# MAIN_POWER.net
KiCad netlist of a schematic drawn in Altium Designer
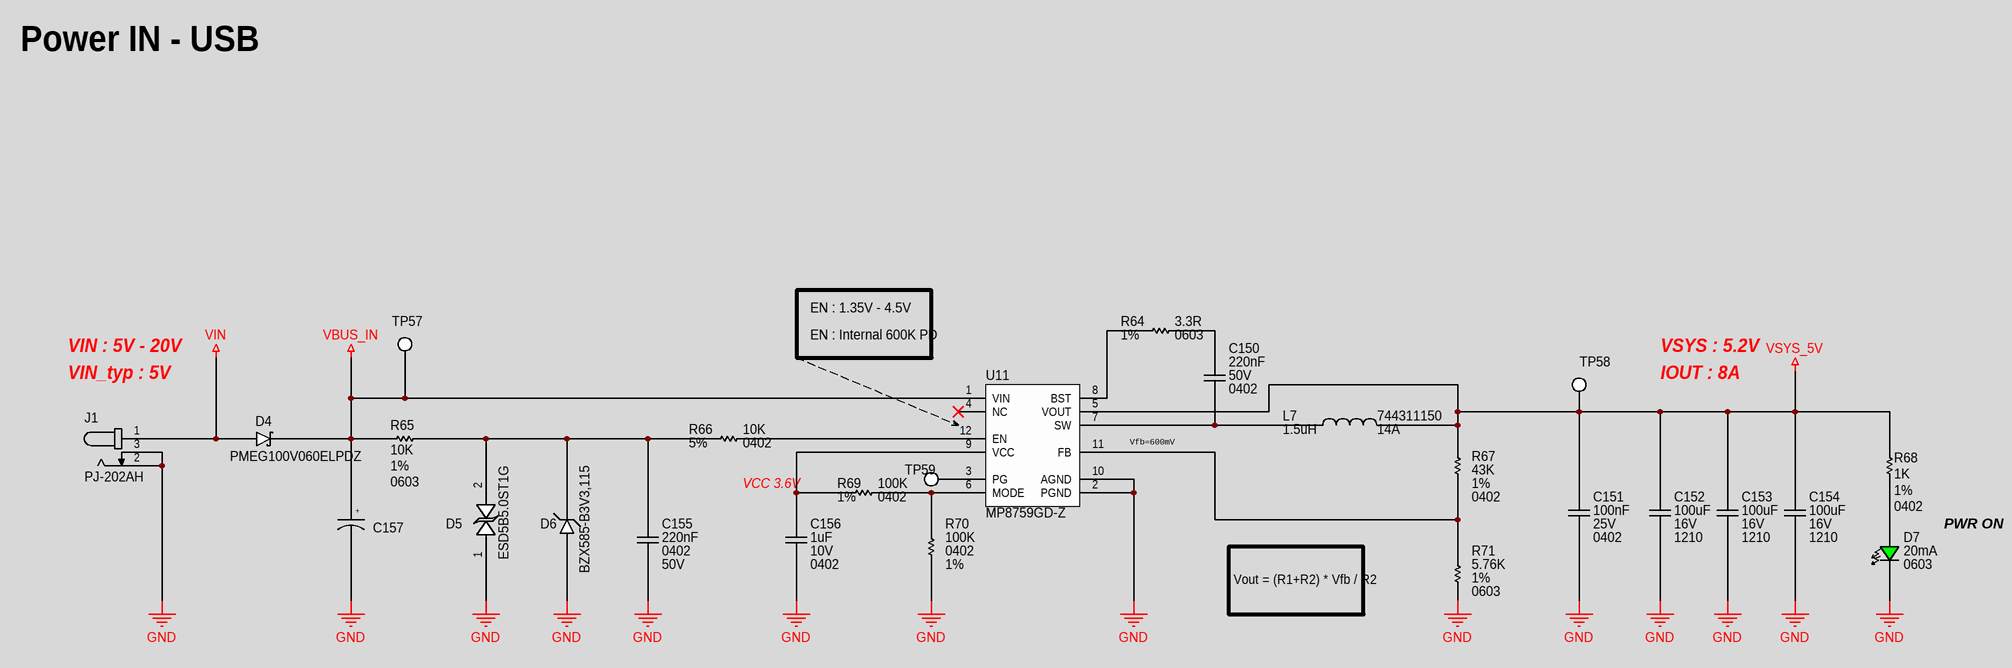
[diagram p0: MAIN_POWER.SchDoc]

(export (version "E")
  (design (tool "Eeschema 10.0.6"))
  (components
    (comp (ref "C150")
      (value "GRM155R61H224KE01W")
      (footprint "CAP_0402_CAPC1005X05N")
      (description "Multilayer Ceramic Capacitor, 0.22 uF, 50 VDC, ± 10%, X5R, 0402 [1005 Metric]")
      (fields
        (field (name "MANUFACTURER") "Murata")
        (field (name "CASE/PACKAGE") "0402")
        (field (name "VOLTAGE RATING (DC)") "50V")
        (field (name "CAPACITANCE") "220nF")
      )
      (libsource (lib "Electronic Devices_LIB") (part "CAP_0.22UF_50V_X5R_0402"))
    )
    (comp (ref "C151")
      (value "CC0402KRX5R8BB104")
      (footprint "CAP_0402_CAPC1005X05N")
      (description "Multilayer Ceramic Capacitor, 0.1 uF, 25 V, ± 10%, X7R, 0402 [1005 Metric]")
      (fields
        (field (name "MANUFACTURER") "Yageo")
        (field (name "TOLERANCE") "10%")
        (field (name "CAPACITANCE") "100nF")
        (field (name "VOLTAGE RATING") "25V")
        (field (name "CASE/PACKAGE") "0402")
      )
      (libsource (lib "Electronic Devices_LIB") (part "CAP_100NF_25V_X7R_0402"))
    )
    (comp (ref "C152")
      (value "EMK325ABJ107MM-T")
      (footprint "CAP_1210_CAPC3225X270N")
      (description "Multilayer Ceramic Capacitor, 100 uF, 16 V, ± 20%, X5R, 1210 [3225 Metric]")
      (fields
        (field (name "MANUFACTURER") "Taiyo Yuden")
        (field (name "TOLERANCE") "20%")
        (field (name "VOLTAGE RATING") "16V")
        (field (name "CAPACITANCE") "100uF")
        (field (name "CASE/PACKAGE") "1210")
      )
      (libsource (lib "Electronic Devices_LIB") (part "CAP_100UF_16V_X5R_1210"))
    )
    (comp (ref "C153")
      (value "EMK325ABJ107MM-T")
      (footprint "CAP_1210_CAPC3225X270N")
      (description "Multilayer Ceramic Capacitor, 100 uF, 16 V, ± 20%, X5R, 1210 [3225 Metric]")
      (fields
        (field (name "MANUFACTURER") "Taiyo Yuden")
        (field (name "TOLERANCE") "20%")
        (field (name "VOLTAGE RATING") "16V")
        (field (name "CAPACITANCE") "100uF")
        (field (name "CASE/PACKAGE") "1210")
      )
      (libsource (lib "Electronic Devices_LIB") (part "CAP_100UF_16V_X5R_1210"))
    )
    (comp (ref "C154")
      (value "EMK325ABJ107MM-T")
      (footprint "CAP_1210_CAPC3225X270N")
      (description "Multilayer Ceramic Capacitor, 100 uF, 16 V, ± 20%, X5R, 1210 [3225 Metric]")
      (fields
        (field (name "MANUFACTURER") "Taiyo Yuden")
        (field (name "TOLERANCE") "20%")
        (field (name "VOLTAGE RATING") "16V")
        (field (name "CAPACITANCE") "100uF")
        (field (name "CASE/PACKAGE") "1210")
      )
      (libsource (lib "Electronic Devices_LIB") (part "CAP_100UF_16V_X5R_1210"))
    )
    (comp (ref "C155")
      (value "GRM155R61H224KE01W")
      (footprint "CAP_0402_CAPC1005X05N")
      (description "Multilayer Ceramic Capacitor, 0.22 uF, 50 VDC, ± 10%, X5R, 0402 [1005 Metric]")
      (fields
        (field (name "MANUFACTURER") "Murata")
        (field (name "CASE/PACKAGE") "0402")
        (field (name "VOLTAGE RATING (DC)") "50V")
        (field (name "CAPACITANCE") "220nF")
      )
      (libsource (lib "Electronic Devices_LIB") (part "CAP_0.22UF_50V_X5R_0402"))
    )
    (comp (ref "C156")
      (value "GRM155C81A105KA12D")
      (footprint "CAP_0402_CAPC1005X05N")
      (description "0402 10 V 1 uF ±10% Tolerance X6S Multilayer Ceramic Capacitor")
      (fields
        (field (name "MANUFACTURER") "Murata")
        (field (name "TOLERANCE") "10%")
        (field (name "VOLTAGE RATING") "10V")
        (field (name "CAPACITANCE") "1uF")
        (field (name "CASE/PACKAGE") "0402")
      )
      (libsource (lib "Electronic Devices_LIB") (part "CAP_1UF_10V_X6S_0402"))
    )
    (comp (ref "C157")
      (value "UUD1H101MNL1GS")
      (footprint "CAP_POLA_UD(8X10)")
      (description "Radial Can - SMD ALUMINUM ELECTROLYTIC CAPACITOR UUD 50V 100muF ±20% 0.315Dia 8.00mm")
      (fields (field (name "MANUFACTURER") "Nichicon") (field (name "TOLERANCE") "20%"))
      (libsource (lib "Electronic Devices_LIB") (part "CAP_100UF_50V_POL"))
    )
    (comp (ref "D4")
      (value "PMEG100V060ELPDZ")
      (footprint "DIO_SCKTY_PMEG060V100EPDAZ")
      (description "DIODESCHOTTKY100V6ACFP15")
      (fields (field (name "MANUFACTURER") "Nexperia"))
      (libsource (lib "Electronic Devices_LIB") (part "DIO_SCTKY_100V_6A_PMEG100V060ELPDZ"))
    )
    (comp (ref "D5")
      (value "ESD5B5.0ST1G")
      (footprint "DIO_TVS_SODFL1608X70N")
      (description "ESD5B5.0S Series 5.8 V 50 W 32 pF SMT ESD Protection Diode - SOD-523")
      (libsource (lib "Electronic Devices_LIB") (part "DIO_TVS_5.8V_ESD5B5.0ST1G_1"))
    )
    (comp (ref "D6")
      (value "BZX585-B3V3,115")
      (footprint "DIO_ZENER_BZX585B3V3115")
      (description "DIODE ZENER 3.3V 300MW SOD523")
      (fields (field (name "MANUFACTURER") "Nexperia"))
      (libsource (lib "Electronic Devices_LIB") (part "DIO_ZENER_3.3V_300mW_BZX585-B3V3,115"))
    )
    (comp (ref "D7")
      (value "LTST-C191KGKT")
      (footprint "LED_0603-GREEN")
      (description "LTST-C191KGKT Lite-On LED, green, 18-71mcd, 130, 1.9V-2.4V SMD, 0603 1.6x0.8x0.55mm RoHS")
      (fields
        (field (name "MANUFACTURER") "Vishay Lite-On")
        (field (name "TEST CURRENT") "20mA")
        (field (name "CASE/PACKAGE") "0603")
      )
      (libsource (lib "Electronic Devices_LIB") (part "LED_DIO_GREEN_20mA_0603"))
    )
    (comp (ref "J1")
      (value "PJ-202AH")
      (footprint "CONN_CUI_PJ-202AH")
      (description "2.0 x 6.5 mm, 5.0 A, Horizontal, Through Hole, Kinked Pins, Dc Power Jack Connector")
      (fields (field (name "MANUFACTURER") "CUI Devices"))
      (libsource (lib "Electronic Devices_LIB") (part "CONN_DC_JACK_2X6.5mm_PJ-202AH"))
    )
    (comp (ref "L7")
      (value "744311150")
      (footprint "IND_WE-HCI_7030/7040/705023")
      (description "Power Choke Shielded Wirewound 1.5uH/1.12uH 20% 100KHz 11A 6.6mOhm DCR T/R")
      (fields
        (field (name "MANUFACTURER") "Wurth Electronics")
        (field (name "TOLERANCE") "20%")
        (field (name "SATURATION CURRENT") "14A")
        (field (name "INDUCTANCE") "1.5uH")
      )
      (libsource (lib "Electronic Devices_LIB") (part "IND_1.5uH_11A_744311150"))
    )
    (comp (ref "R64")
      (value "RK73H1JTTD3R30F")
      (footprint "RES_0603_RESC1608X04N")
      (description "Thick Film Chip Resistor 0603 SMD 3.3 Ohm 1% 0.125W(1/8W) 200ppm/C")
      (fields
        (field (name "MANUFACTURER") "KOA Speer")
        (field (name "TOLERANCE") "1%")
        (field (name "RESISTANCE") "3.3R")
        (field (name "CASE CODE (IMPERIAL)") "0603")
      )
      (libsource (lib "Electronic Devices_LIB") (part "RES_3.3R_1%_125mW_0603"))
    )
    (comp (ref "R65")
      (value "AC0603FR-1010KL")
      (footprint "RES_0603_RESC1608X04N")
      (description "Chip Resistor Automotive Grade Thick Film 0603 10kOhm 1% Paper T/R")
      (fields
        (field (name "MANUFACTURER") "Yageo")
        (field (name "RESISTANCE") "10K")
        (field (name "TOLERANCE") "1%")
        (field (name "CASE/PACKAGE") "0603")
      )
      (libsource (lib "Electronic Devices_LIB") (part "RES_10K_1%_100mW_0603"))
    )
    (comp (ref "R66")
      (value "ERJ-2GEJ103X")
      (footprint "RES_0402_RESC1005X04N")
      (description "Res Thick Film 0402 10K Ohm 5% 1/10W ±200ppm/°C Molded SMD Punched Carrier T/R")
      (fields
        (field (name "MANUFACTURER") "Panasonic")
        (field (name "TOLERANCE") "5%")
        (field (name "RESISTANCE") "10K")
        (field (name "CASE/PACKAGE") "0402")
      )
      (libsource (lib "Electronic Devices_LIB") (part "RES_10K_5%_100mW_0402"))
    )
    (comp (ref "R67")
      (value "CRCW040243K0FKED")
      (footprint "RES_0402_RESC1005X04N")
      (description "SMD Chip Resistor, 43 kOhm, ± 1%, 63 mW, 0402 [1005 Metric], Thick Film, General Purpose")
      (fields
        (field (name "MANUFACTURER") "Vishay")
        (field (name "TOLERANCE") "1%")
        (field (name "RESISTANCE") "43K")
        (field (name "CASE/PACKAGE") "0402")
      )
      (libsource (lib "Electronic Devices_LIB") (part "RES_43K_1%_63mW_0402"))
    )
    (comp (ref "R68")
      (value "ERJ-2RKF1001X")
      (footprint "RES_0402_RESC1005X04N")
      (description "RES SMD 1K OHM 1% 1/10W 0402")
      (fields
        (field (name "MANUFACTURER") "Panasonic")
        (field (name "RESISTANCE") "1K")
        (field (name "TOLERANCE") "1%")
        (field (name "CASE/PACKAGE") "0402")
      )
      (libsource (lib "Electronic Devices_LIB") (part "RES_1K_1%_100mW_0402"))
    )
    (comp (ref "R69")
      (value "RC0402FR-07100KL")
      (footprint "RES_0402_RESC1005X04N")
      (description "SMD Chip Resistor, 100 kOhm, ± 1%, 63 mW, 0402 [1005 Metric], Thick Film, General Purpose")
      (fields
        (field (name "MANUFACTURER") "Yageo")
        (field (name "RESISTANCE") "100K")
        (field (name "TOLERANCE") "1%")
        (field (name "CASE/PACKAGE") "0402")
      )
      (libsource (lib "Electronic Devices_LIB") (part "RES_100K_1%_100mW_0402"))
    )
    (comp (ref "R70")
      (value "RC0402FR-07100KL")
      (footprint "RES_0402_RESC1005X04N")
      (description "SMD Chip Resistor, 100 kOhm, ± 1%, 63 mW, 0402 [1005 Metric], Thick Film, General Purpose")
      (fields
        (field (name "MANUFACTURER") "Yageo")
        (field (name "RESISTANCE") "100K")
        (field (name "TOLERANCE") "1%")
        (field (name "CASE/PACKAGE") "0402")
      )
      (libsource (lib "Electronic Devices_LIB") (part "RES_100K_1%_100mW_0402"))
    )
    (comp (ref "R71")
      (value "RC0603FR-075K76L")
      (footprint "RES_0603_RESC1608X04N")
      (description "SMD Chip Resistor, 5.76 kOhm, ± 1%, 100 mW, 0603 [1608 Metric], Thick Film, General Purpose")
      (fields
        (field (name "MANUFACTURER") "Yageo")
        (field (name "TOLERANCE") "1%")
        (field (name "RESISTANCE") "5.76K")
        (field (name "CASE/PACKAGE") "0603")
      )
      (libsource (lib "Electronic Devices_LIB") (part "RES_5.7K_1%_100mW_0603"))
    )
    (comp (ref "TP57")
      (value "NO COMPONENT")
      (footprint "TP_PAD_0.8MM_SMD_ROUND")
      (description "Test Point, SMD pad, round, 1.5mm, 1.6mm, 3mm diameter")
      (libsource (lib "Electronic Devices_LIB") (part "TP_PAD_SMD_Round"))
    )
    (comp (ref "TP58")
      (value "NO COMPONENT")
      (footprint "TP_PAD_0.8MM_SMD_ROUND")
      (description "Test Point, SMD pad, round, 1.5mm, 1.6mm, 3mm diameter")
      (libsource (lib "Electronic Devices_LIB") (part "TP_PAD_SMD_Round"))
    )
    (comp (ref "TP59")
      (value "NO COMPONENT")
      (footprint "TP_PAD_1.6MM_SMD_ROUND")
      (description "Test Point, SMD pad, round, 1.5mm, 1.6mm, 3mm diameter")
      (libsource (lib "Electronic Devices_LIB") (part "TP_PAD_SMD_Round"))
    )
    (comp (ref "U11")
      (value "MP8759GD-Z")
      (footprint "IC_REG_MP8759GDZ")
      (description "Tape & Reel (TR) Active Step-Down Buck DC to DC switching regulator 26V 8A 700kHz -40C~125C TJ")
      (fields (field (name "MANUFACTURER") "Monolithic Power Systems"))
      (libsource (lib "Electronic Devices_LIB") (part "IC_REG_BUCK_26V_8A_MP8759GD-Z"))
    )
  )
  (nets
    (net (code "1") (name "GND") (class "Default")
      (node (ref "C151") (pin "1") (pinfunction "1_1") (pintype "passive"))
      (node (ref "C152") (pin "1") (pinfunction "1_1") (pintype "passive"))
      (node (ref "C153") (pin "1") (pinfunction "1_1") (pintype "passive"))
      (node (ref "C154") (pin "1") (pinfunction "1_1") (pintype "passive"))
      (node (ref "C155") (pin "1") (pinfunction "1_1") (pintype "passive"))
      (node (ref "C156") (pin "1") (pinfunction "1_1") (pintype "passive"))
      (node (ref "C157") (pin "2") (pinfunction "2_2") (pintype "passive"))
      (node (ref "D5") (pin "1") (pinfunction "A1_1") (pintype "passive"))
      (node (ref "D6") (pin "2") (pinfunction "A_2") (pintype "passive"))
      (node (ref "D7") (pin "1") (pinfunction "C_1") (pintype "passive"))
      (node (ref "J1") (pin "2") (pinfunction "2_2") (pintype "passive"))
      (node (ref "J1") (pin "3") (pinfunction "3_3") (pintype "passive"))
      (node (ref "R70") (pin "1") (pinfunction "1_1") (pintype "passive"))
      (node (ref "R71") (pin "1") (pinfunction "1_1") (pintype "passive"))
      (node (ref "U11") (pin "10") (pinfunction "AGND_10") (pintype "passive"))
      (node (ref "U11") (pin "2") (pinfunction "PGND_2") (pintype "passive"))
    )
    (net (code "2") (name "Net-(C150-Pad2)") (class "Default")
      (node (ref "C150") (pin "2") (pinfunction "2_2") (pintype "passive"))
      (node (ref "R64") (pin "2") (pinfunction "2_2") (pintype "passive"))
    )
    (net (code "3") (name "Net-(D5-A2)") (class "Default")
      (node (ref "C155") (pin "2") (pinfunction "2_2") (pintype "passive"))
      (node (ref "D5") (pin "2") (pinfunction "A2_2") (pintype "passive"))
      (node (ref "D6") (pin "1") (pinfunction "K_1") (pintype "passive"))
      (node (ref "R65") (pin "1") (pinfunction "1_1") (pintype "passive"))
      (node (ref "R66") (pin "1") (pinfunction "1_1") (pintype "passive"))
    )
    (net (code "4") (name "Net-(D7-A)") (class "Default")
      (node (ref "D7") (pin "2") (pinfunction "A_2") (pintype "passive"))
      (node (ref "R68") (pin "1") (pinfunction "1_1") (pintype "passive"))
    )
    (net (code "5") (name "Net-(U11-BST)") (class "Default")
      (node (ref "R64") (pin "1") (pinfunction "1_1") (pintype "passive"))
      (node (ref "U11") (pin "8") (pinfunction "BST_8") (pintype "passive"))
    )
    (net (code "6") (name "Net-(U11-EN)") (class "Default")
      (node (ref "R66") (pin "2") (pinfunction "2_2") (pintype "passive"))
      (node (ref "U11") (pin "12") (pinfunction "EN_12") (pintype "passive"))
    )
    (net (code "7") (name "Net-(U11-FB)") (class "Default")
      (node (ref "R67") (pin "1") (pinfunction "1_1") (pintype "passive"))
      (node (ref "R71") (pin "2") (pinfunction "2_2") (pintype "passive"))
      (node (ref "U11") (pin "11") (pinfunction "FB_11") (pintype "passive"))
    )
    (net (code "8") (name "Net-(U11-MODE)") (class "Default")
      (node (ref "R69") (pin "2") (pinfunction "2_2") (pintype "passive"))
      (node (ref "R70") (pin "2") (pinfunction "2_2") (pintype "passive"))
      (node (ref "U11") (pin "6") (pinfunction "MODE_6") (pintype "passive"))
    )
    (net (code "9") (name "Net-(U11-PG)") (class "Default")
      (node (ref "TP59") (pin "1") (pinfunction "1_1") (pintype "passive"))
      (node (ref "U11") (pin "3") (pinfunction "PG_3") (pintype "passive"))
    )
    (net (code "10") (name "Net-(U11-SW)") (class "Default")
      (node (ref "C150") (pin "1") (pinfunction "1_1") (pintype "passive"))
      (node (ref "L7") (pin "1") (pinfunction "1_1") (pintype "passive"))
      (node (ref "U11") (pin "7") (pinfunction "SW_7") (pintype "passive"))
    )
    (net (code "11") (name "Net-(U11-VCC)") (class "Default")
      (node (ref "C156") (pin "2") (pinfunction "2_2") (pintype "passive"))
      (node (ref "R69") (pin "1") (pinfunction "1_1") (pintype "passive"))
      (node (ref "U11") (pin "9") (pinfunction "VCC_9") (pintype "passive"))
    )
    (net (code "12") (name "VBUS_IN") (class "Default")
      (node (ref "C157") (pin "1") (pinfunction "1_1") (pintype "passive"))
      (node (ref "D4") (pin "K") (pinfunction "K_K") (pintype "passive"))
      (node (ref "R65") (pin "2") (pinfunction "2_2") (pintype "passive"))
      (node (ref "TP57") (pin "1") (pinfunction "1_1") (pintype "passive"))
      (node (ref "U11") (pin "1") (pinfunction "VIN_1") (pintype "passive"))
    )
    (net (code "13") (name "VIN") (class "Default")
      (node (ref "D4") (pin "A") (pinfunction "A_A") (pintype "passive"))
      (node (ref "J1") (pin "1") (pinfunction "1_1") (pintype "passive"))
    )
    (net (code "14") (name "VSYS_5V") (class "Default")
      (node (ref "C151") (pin "2") (pinfunction "2_2") (pintype "passive"))
      (node (ref "C152") (pin "2") (pinfunction "2_2") (pintype "passive"))
      (node (ref "C153") (pin "2") (pinfunction "2_2") (pintype "passive"))
      (node (ref "C154") (pin "2") (pinfunction "2_2") (pintype "passive"))
      (node (ref "L7") (pin "2") (pinfunction "2_2") (pintype "passive"))
      (node (ref "R67") (pin "2") (pinfunction "2_2") (pintype "passive"))
      (node (ref "R68") (pin "2") (pinfunction "2_2") (pintype "passive"))
      (node (ref "TP58") (pin "1") (pinfunction "1_1") (pintype "passive"))
      (node (ref "U11") (pin "5") (pinfunction "VOUT_5") (pintype "passive"))
    )
    (net (code "15") (name "unconnected-(U11-NC-Pad4)") (class "Default")
      (node (ref "U11") (pin "4") (pinfunction "NC_4") (pintype "passive+no_connect"))
    )
  )
)
